# Interlock_Multiplexer.net
KiCad netlist of a schematic drawn in Altium Designer
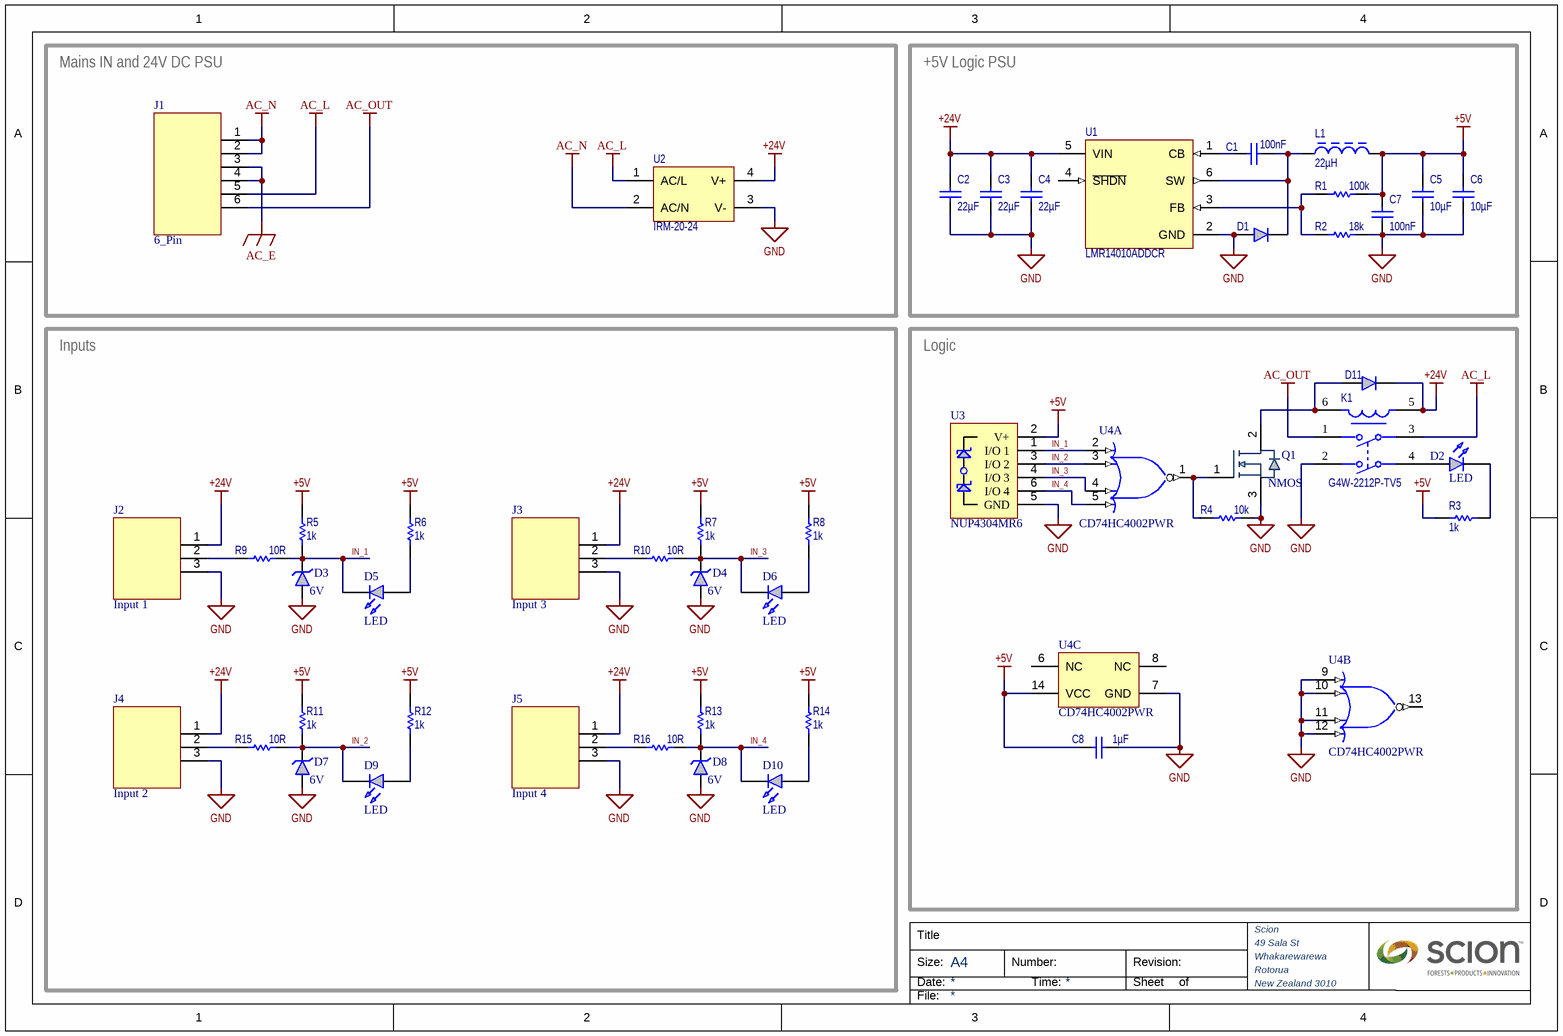
[diagram p0: Interlock Multiplexer.SchDoc]

(export (version "E")
  (design (tool "Eeschema 10.0.6"))
  (components
    (comp (ref "C1")
      (value "100nF")
      (footprint "0603_CAP")
      (description "SMD Capacitor")
      (fields (field (name "Comment") "Capacitor"))
      (libsource (lib "Scion Research") (part "CMP-019-00005-2"))
    )
    (comp (ref "C2")
      (value "22µF")
      (footprint "1206_CAP")
      (description "SMD Capacitor")
      (fields (field (name "Comment") "Capacitor"))
      (libsource (lib "Scion Research") (part "CMP-019-00005-2"))
    )
    (comp (ref "C3")
      (value "22µF")
      (footprint "1206_CAP")
      (description "SMD Capacitor")
      (fields (field (name "Comment") "Capacitor"))
      (libsource (lib "Scion Research") (part "CMP-019-00005-2"))
    )
    (comp (ref "C4")
      (value "22µF")
      (footprint "1206_CAP")
      (description "SMD Capacitor")
      (fields (field (name "Comment") "Capacitor"))
      (libsource (lib "Scion Research") (part "CMP-019-00005-2"))
    )
    (comp (ref "C5")
      (value "10µF")
      (footprint "0603_CAP")
      (description "SMD Capacitor")
      (fields (field (name "Comment") "Capacitor"))
      (libsource (lib "Scion Research") (part "CMP-019-00005-2"))
    )
    (comp (ref "C6")
      (value "10µF")
      (footprint "0603_CAP")
      (description "SMD Capacitor")
      (fields (field (name "Comment") "Capacitor"))
      (libsource (lib "Scion Research") (part "CMP-019-00005-2"))
    )
    (comp (ref "C7")
      (value "100nF")
      (footprint "0603_CAP")
      (description "SMD Capacitor")
      (fields (field (name "Comment") "Capacitor"))
      (libsource (lib "Scion Research") (part "CMP-019-00005-2"))
    )
    (comp (ref "C8")
      (value "1µF")
      (footprint "0603_CAP")
      (description "SMD Capacitor")
      (fields (field (name "Comment") "Capacitor"))
      (libsource (lib "Scion Research") (part "CMP-019-00005-2"))
    )
    (comp (ref "D1")
      (value "Diode")
      (footprint "SOD-123")
      (description "SMD Diode")
      (libsource (lib "Scion Research") (part "Diode"))
    )
    (comp (ref "D2")
      (value "LED")
      (footprint "0805")
      (description "SMD LED")
      (libsource (lib "Scion Research") (part "CMP-004-00032-1"))
    )
    (comp (ref "D3")
      (value "Transil")
      (footprint "SMBJ")
      (description "Transient Voltage Suppressor")
      (fields (field (name "RATED VOLTAGE") "6V"))
      (libsource (lib "Scion Research") (part "CMP-004-0042-1"))
    )
    (comp (ref "D4")
      (value "Transil")
      (footprint "SMBJ")
      (description "Transient Voltage Suppressor")
      (fields (field (name "RATED VOLTAGE") "6V"))
      (libsource (lib "Scion Research") (part "CMP-004-0042-1"))
    )
    (comp (ref "D5")
      (value "LED")
      (footprint "0805")
      (description "SMD LED")
      (libsource (lib "Scion Research") (part "CMP-004-00032-1"))
    )
    (comp (ref "D6")
      (value "LED")
      (footprint "0805")
      (description "SMD LED")
      (libsource (lib "Scion Research") (part "CMP-004-00032-1"))
    )
    (comp (ref "D7")
      (value "Transil")
      (footprint "SMBJ")
      (description "Transient Voltage Suppressor")
      (fields (field (name "RATED VOLTAGE") "6V"))
      (libsource (lib "Scion Research") (part "CMP-004-0042-1"))
    )
    (comp (ref "D8")
      (value "Transil")
      (footprint "SMBJ")
      (description "Transient Voltage Suppressor")
      (fields (field (name "RATED VOLTAGE") "6V"))
      (libsource (lib "Scion Research") (part "CMP-004-0042-1"))
    )
    (comp (ref "D9")
      (value "LED")
      (footprint "0805")
      (description "SMD LED")
      (libsource (lib "Scion Research") (part "CMP-004-00032-1"))
    )
    (comp (ref "D10")
      (value "LED")
      (footprint "0805")
      (description "SMD LED")
      (libsource (lib "Scion Research") (part "CMP-004-00032-1"))
    )
    (comp (ref "D11")
      (value "Diode")
      (footprint "SOD-123")
      (description "SMD Diode")
      (libsource (lib "Scion Research") (part "Diode"))
    )
    (comp (ref "J1")
      (value "6_Pin")
      (footprint "TDPT 6p 5.08")
      (description "6 Pin Connector")
      (libsource (lib "Scion Research") (part "CMP-002-00081-5"))
    )
    (comp (ref "J2")
      (value "Input 1")
      (footprint "3_Pin 3.81mm Molex 395111-003")
      (description "3 Pin Connector")
      (libsource (lib "Scion Research") (part "CMP-002-00075-6"))
    )
    (comp (ref "J3")
      (value "Input 3")
      (footprint "3_Pin 3.81mm Molex 395111-003")
      (description "3 Pin Connector")
      (libsource (lib "Scion Research") (part "CMP-002-00075-6"))
    )
    (comp (ref "J4")
      (value "Input 2")
      (footprint "3_Pin 3.81mm Molex 395111-003")
      (description "3 Pin Connector")
      (libsource (lib "Scion Research") (part "CMP-002-00075-6"))
    )
    (comp (ref "J5")
      (value "Input 4")
      (footprint "3_Pin 3.81mm Molex 395111-003")
      (description "3 Pin Connector")
      (libsource (lib "Scion Research") (part "CMP-002-00075-6"))
    )
    (comp (ref "K1")
      (value "G4W-2212P-TV5")
      (footprint "G4W-2212P-US-TV5 24VDC-Footprint-1")
      (description "DPNO 10A 24VDC Relay")
      (libsource (lib "Scion Research") (part "CMP-00056-1"))
    )
    (comp (ref "L1")
      (value "22µH")
      (footprint "BOUR-SRN8040_V")
      (description "Power Inductor")
      (fields (field (name "Comment") "Inductor"))
      (libsource (lib "Scion Research") (part "Inductor"))
    )
    (comp (ref "Q1")
      (value "NMOS")
      (footprint "SOT-23")
      (description "N Channel MOSFET")
      (libsource (lib "Scion Research") (part "CMP-004-0025-1"))
    )
    (comp (ref "R1")
      (value "Resistor")
      (footprint "0603_RES")
      (description "SMD Resistor")
      (fields (field (name "ALTIUM_VALUE") "100k"))
      (libsource (lib "Scion Research") (part "CMP-009-00177-2"))
    )
    (comp (ref "R2")
      (value "Resistor")
      (footprint "0603_RES")
      (description "SMD Resistor")
      (fields (field (name "ALTIUM_VALUE") "18k"))
      (libsource (lib "Scion Research") (part "CMP-009-00177-2"))
    )
    (comp (ref "R3")
      (value "Resistor")
      (footprint "0603_RES")
      (description "SMD Resistor")
      (fields (field (name "ALTIUM_VALUE") "1k"))
      (libsource (lib "Scion Research") (part "CMP-009-00177-2"))
    )
    (comp (ref "R4")
      (value "Resistor")
      (footprint "0603_RES")
      (description "SMD Resistor")
      (fields (field (name "ALTIUM_VALUE") "10k"))
      (libsource (lib "Scion Research") (part "CMP-009-00177-2"))
    )
    (comp (ref "R5")
      (value "Resistor")
      (footprint "0603_RES")
      (description "SMD Resistor")
      (fields (field (name "ALTIUM_VALUE") "1k"))
      (libsource (lib "Scion Research") (part "CMP-009-00177-2"))
    )
    (comp (ref "R6")
      (value "Resistor")
      (footprint "0603_RES")
      (description "SMD Resistor")
      (fields (field (name "ALTIUM_VALUE") "1k"))
      (libsource (lib "Scion Research") (part "CMP-009-00177-2"))
    )
    (comp (ref "R7")
      (value "Resistor")
      (footprint "0603_RES")
      (description "SMD Resistor")
      (fields (field (name "ALTIUM_VALUE") "1k"))
      (libsource (lib "Scion Research") (part "CMP-009-00177-2"))
    )
    (comp (ref "R8")
      (value "Resistor")
      (footprint "0603_RES")
      (description "SMD Resistor")
      (fields (field (name "ALTIUM_VALUE") "1k"))
      (libsource (lib "Scion Research") (part "CMP-009-00177-2"))
    )
    (comp (ref "R9")
      (value "Resistor")
      (footprint "0603_RES")
      (description "SMD Resistor")
      (fields (field (name "ALTIUM_VALUE") "10R"))
      (libsource (lib "Scion Research") (part "CMP-009-00177-2"))
    )
    (comp (ref "R10")
      (value "Resistor")
      (footprint "0603_RES")
      (description "SMD Resistor")
      (fields (field (name "ALTIUM_VALUE") "10R"))
      (libsource (lib "Scion Research") (part "CMP-009-00177-2"))
    )
    (comp (ref "R11")
      (value "Resistor")
      (footprint "0603_RES")
      (description "SMD Resistor")
      (fields (field (name "ALTIUM_VALUE") "1k"))
      (libsource (lib "Scion Research") (part "CMP-009-00177-2"))
    )
    (comp (ref "R12")
      (value "Resistor")
      (footprint "0603_RES")
      (description "SMD Resistor")
      (fields (field (name "ALTIUM_VALUE") "1k"))
      (libsource (lib "Scion Research") (part "CMP-009-00177-2"))
    )
    (comp (ref "R13")
      (value "Resistor")
      (footprint "0603_RES")
      (description "SMD Resistor")
      (fields (field (name "ALTIUM_VALUE") "1k"))
      (libsource (lib "Scion Research") (part "CMP-009-00177-2"))
    )
    (comp (ref "R14")
      (value "Resistor")
      (footprint "0603_RES")
      (description "SMD Resistor")
      (fields (field (name "ALTIUM_VALUE") "1k"))
      (libsource (lib "Scion Research") (part "CMP-009-00177-2"))
    )
    (comp (ref "R15")
      (value "Resistor")
      (footprint "0603_RES")
      (description "SMD Resistor")
      (fields (field (name "ALTIUM_VALUE") "10R"))
      (libsource (lib "Scion Research") (part "CMP-009-00177-2"))
    )
    (comp (ref "R16")
      (value "Resistor")
      (footprint "0603_RES")
      (description "SMD Resistor")
      (fields (field (name "ALTIUM_VALUE") "10R"))
      (libsource (lib "Scion Research") (part "CMP-009-00177-2"))
    )
    (comp (ref "U1")
      (value "LMR14010ADDCR")
      (footprint "FP-DDC0006A-IPC_A")
      (description "7-40VDC-DC buck converter")
      (libsource (lib "Scion Research") (part "LMR14010"))
    )
    (comp (ref "U2")
      (value "IRM-20-24")
      (footprint "IRM-20-24-Footprint-1")
      (description "AC/DC 20W 24V Single Output Power Supply, Encapsulated Board Mount Module")
      (libsource (lib "Scion Research") (part "CMP-00053-2"))
    )
    (comp (ref "U3")
      (value "NUP4304MR6")
      (footprint "TSOP-6")
      (description "ESD Protection Doide Array")
      (libsource (lib "Scion Research") (part "CMP-004-0028-1"))
    )
    (comp (ref "U4")
      (value "CD74HC4002PWR")
      (footprint "PW0014A_N")
      (description "NOR Gate, HC Series, 2-Func, 4-Input, CMOS, PDSO14")
      (libsource (lib "Scion Research") (part "TI-CD_SNX4HC4002-14"))
    )
  )
  (nets
    (net (code "1") (name "+5V") (class "Default")
      (node (ref "C5") (pin "1") (pinfunction "1_1") (pintype "passive"))
      (node (ref "C6") (pin "1") (pinfunction "1_1") (pintype "passive"))
      (node (ref "C7") (pin "1") (pinfunction "1_1") (pintype "passive"))
      (node (ref "C8") (pin "1") (pinfunction "1_1") (pintype "passive"))
      (node (ref "L1") (pin "2") (pinfunction "2_2") (pintype "passive"))
      (node (ref "R1") (pin "2") (pinfunction "2_2") (pintype "passive"))
      (node (ref "R11") (pin "2") (pinfunction "2_2") (pintype "passive"))
      (node (ref "R12") (pin "2") (pinfunction "2_2") (pintype "passive"))
      (node (ref "R13") (pin "2") (pinfunction "2_2") (pintype "passive"))
      (node (ref "R14") (pin "2") (pinfunction "2_2") (pintype "passive"))
      (node (ref "R3") (pin "2") (pinfunction "2_2") (pintype "passive"))
      (node (ref "R5") (pin "2") (pinfunction "2_2") (pintype "passive"))
      (node (ref "R6") (pin "2") (pinfunction "2_2") (pintype "passive"))
      (node (ref "R7") (pin "2") (pinfunction "2_2") (pintype "passive"))
      (node (ref "R8") (pin "2") (pinfunction "2_2") (pintype "passive"))
      (node (ref "U3") (pin "2") (pinfunction "V+_2") (pintype "power_in"))
      (node (ref "U4") (pin "14") (pinfunction "VCC_14") (pintype "power_in"))
    )
    (net (code "2") (name "+24V") (class "Default")
      (node (ref "C2") (pin "1") (pinfunction "1_1") (pintype "passive"))
      (node (ref "C3") (pin "1") (pinfunction "1_1") (pintype "passive"))
      (node (ref "C4") (pin "1") (pinfunction "1_1") (pintype "passive"))
      (node (ref "D11") (pin "1") (pinfunction "K_1") (pintype "passive"))
      (node (ref "J2") (pin "1") (pinfunction "1_1") (pintype "passive"))
      (node (ref "J3") (pin "1") (pinfunction "1_1") (pintype "passive"))
      (node (ref "J4") (pin "1") (pinfunction "1_1") (pintype "passive"))
      (node (ref "J5") (pin "1") (pinfunction "1_1") (pintype "passive"))
      (node (ref "K1") (pin "5") (pinfunction "5_5") (pintype "passive"))
      (node (ref "U1") (pin "5") (pinfunction "VIN_5") (pintype "power_in"))
      (node (ref "U2") (pin "4") (pinfunction "V+_4") (pintype "power_in"))
    )
    (net (code "3") (name "/IN_1") (class "Default")
      (node (ref "D3") (pin "2") (pinfunction "K_2") (pintype "passive"))
      (node (ref "D5") (pin "1") (pinfunction "K_1") (pintype "passive"))
      (node (ref "R5") (pin "1") (pinfunction "1_1") (pintype "passive"))
      (node (ref "R9") (pin "2") (pinfunction "2_2") (pintype "passive"))
      (node (ref "U3") (pin "1") (pinfunction "I/O_1_1") (pintype "power_in"))
      (node (ref "U4") (pin "2") (pinfunction "1A_2") (pintype "input"))
    )
    (net (code "4") (name "/IN_2") (class "Default")
      (node (ref "D7") (pin "2") (pinfunction "K_2") (pintype "passive"))
      (node (ref "D9") (pin "1") (pinfunction "K_1") (pintype "passive"))
      (node (ref "R11") (pin "1") (pinfunction "1_1") (pintype "passive"))
      (node (ref "R15") (pin "2") (pinfunction "2_2") (pintype "passive"))
      (node (ref "U3") (pin "3") (pinfunction "I/O_2_3") (pintype "power_in"))
      (node (ref "U4") (pin "3") (pinfunction "1B_3") (pintype "input"))
    )
    (net (code "5") (name "/IN_3") (class "Default")
      (node (ref "D4") (pin "2") (pinfunction "K_2") (pintype "passive"))
      (node (ref "D6") (pin "1") (pinfunction "K_1") (pintype "passive"))
      (node (ref "R10") (pin "2") (pinfunction "2_2") (pintype "passive"))
      (node (ref "R7") (pin "1") (pinfunction "1_1") (pintype "passive"))
      (node (ref "U3") (pin "4") (pinfunction "I/O_3_4") (pintype "power_in"))
      (node (ref "U4") (pin "4") (pinfunction "1C_4") (pintype "input"))
    )
    (net (code "6") (name "/IN_4") (class "Default")
      (node (ref "D10") (pin "1") (pinfunction "K_1") (pintype "passive"))
      (node (ref "D8") (pin "2") (pinfunction "K_2") (pintype "passive"))
      (node (ref "R13") (pin "1") (pinfunction "1_1") (pintype "passive"))
      (node (ref "R16") (pin "2") (pinfunction "2_2") (pintype "passive"))
      (node (ref "U3") (pin "6") (pinfunction "I/O_4_6") (pintype "power_in"))
      (node (ref "U4") (pin "5") (pinfunction "1D_5") (pintype "input"))
    )
    (net (code "7") (name "AC_E") (class "Default")
      (node (ref "J1") (pin "3") (pinfunction "3_3") (pintype "passive"))
      (node (ref "J1") (pin "4") (pinfunction "4_4") (pintype "passive"))
    )
    (net (code "8") (name "AC_L") (class "Default")
      (node (ref "J1") (pin "5") (pinfunction "5_5") (pintype "passive"))
      (node (ref "K1") (pin "3") (pinfunction "3_3") (pintype "passive"))
      (node (ref "U2") (pin "1") (pinfunction "AC/L_1") (pintype "passive"))
    )
    (net (code "9") (name "AC_N") (class "Default")
      (node (ref "J1") (pin "1") (pinfunction "1_1") (pintype "passive"))
      (node (ref "J1") (pin "2") (pinfunction "2_2") (pintype "passive"))
      (node (ref "U2") (pin "2") (pinfunction "AC/N_2") (pintype "passive"))
    )
    (net (code "10") (name "AC_OUT") (class "Default")
      (node (ref "J1") (pin "6") (pinfunction "6_6") (pintype "passive"))
      (node (ref "K1") (pin "1") (pinfunction "1_1") (pintype "passive"))
    )
    (net (code "11") (name "GND") (class "Default")
      (node (ref "C2") (pin "2") (pinfunction "2_2") (pintype "passive"))
      (node (ref "C3") (pin "2") (pinfunction "2_2") (pintype "passive"))
      (node (ref "C4") (pin "2") (pinfunction "2_2") (pintype "passive"))
      (node (ref "C5") (pin "2") (pinfunction "2_2") (pintype "passive"))
      (node (ref "C6") (pin "2") (pinfunction "2_2") (pintype "passive"))
      (node (ref "C7") (pin "2") (pinfunction "2_2") (pintype "passive"))
      (node (ref "C8") (pin "2") (pinfunction "2_2") (pintype "passive"))
      (node (ref "D1") (pin "2") (pinfunction "A_2") (pintype "passive"))
      (node (ref "D3") (pin "1") (pinfunction "A_1") (pintype "passive"))
      (node (ref "D4") (pin "1") (pinfunction "A_1") (pintype "passive"))
      (node (ref "D7") (pin "1") (pinfunction "A_1") (pintype "passive"))
      (node (ref "D8") (pin "1") (pinfunction "A_1") (pintype "passive"))
      (node (ref "J2") (pin "3") (pinfunction "3_3") (pintype "passive"))
      (node (ref "J3") (pin "3") (pinfunction "3_3") (pintype "passive"))
      (node (ref "J4") (pin "3") (pinfunction "3_3") (pintype "passive"))
      (node (ref "J5") (pin "3") (pinfunction "3_3") (pintype "passive"))
      (node (ref "K1") (pin "2") (pinfunction "2_2") (pintype "passive"))
      (node (ref "Q1") (pin "3") (pinfunction "S_3") (pintype "passive"))
      (node (ref "R2") (pin "2") (pinfunction "2_2") (pintype "passive"))
      (node (ref "R4") (pin "2") (pinfunction "2_2") (pintype "passive"))
      (node (ref "U1") (pin "2") (pinfunction "GND_2") (pintype "power_in"))
      (node (ref "U2") (pin "3") (pinfunction "V-_3") (pintype "power_in"))
      (node (ref "U3") (pin "5") (pinfunction "GND_5") (pintype "power_in"))
      (node (ref "U4") (pin "10") (pinfunction "2B_10") (pintype "input"))
      (node (ref "U4") (pin "11") (pinfunction "2C_11") (pintype "input"))
      (node (ref "U4") (pin "12") (pinfunction "2D_12") (pintype "input"))
      (node (ref "U4") (pin "7") (pinfunction "GND_7") (pintype "power_in"))
      (node (ref "U4") (pin "9") (pinfunction "2A_9") (pintype "input"))
    )
    (net (code "12") (name "Net-(D1-K)") (class "Default")
      (node (ref "C1") (pin "1") (pinfunction "1_1") (pintype "passive"))
      (node (ref "D1") (pin "1") (pinfunction "K_1") (pintype "passive"))
      (node (ref "L1") (pin "1") (pinfunction "1_1") (pintype "passive"))
      (node (ref "U1") (pin "6") (pinfunction "SW_6") (pintype "output"))
    )
    (net (code "13") (name "Net-(D2-A)") (class "Default")
      (node (ref "D2") (pin "2") (pinfunction "A_2") (pintype "passive"))
      (node (ref "K1") (pin "4") (pinfunction "4_4") (pintype "passive"))
    )
    (net (code "14") (name "Net-(D2-K)") (class "Default")
      (node (ref "D2") (pin "1") (pinfunction "K_1") (pintype "passive"))
      (node (ref "R3") (pin "1") (pinfunction "1_1") (pintype "passive"))
    )
    (net (code "15") (name "Net-(D5-A)") (class "Default")
      (node (ref "D5") (pin "2") (pinfunction "A_2") (pintype "passive"))
      (node (ref "R6") (pin "1") (pinfunction "1_1") (pintype "passive"))
    )
    (net (code "16") (name "Net-(D6-A)") (class "Default")
      (node (ref "D6") (pin "2") (pinfunction "A_2") (pintype "passive"))
      (node (ref "R8") (pin "1") (pinfunction "1_1") (pintype "passive"))
    )
    (net (code "17") (name "Net-(D9-A)") (class "Default")
      (node (ref "D9") (pin "2") (pinfunction "A_2") (pintype "passive"))
      (node (ref "R12") (pin "1") (pinfunction "1_1") (pintype "passive"))
    )
    (net (code "18") (name "Net-(D10-A)") (class "Default")
      (node (ref "D10") (pin "2") (pinfunction "A_2") (pintype "passive"))
      (node (ref "R14") (pin "1") (pinfunction "1_1") (pintype "passive"))
    )
    (net (code "19") (name "Net-(D11-A)") (class "Default")
      (node (ref "D11") (pin "2") (pinfunction "A_2") (pintype "passive"))
      (node (ref "K1") (pin "6") (pinfunction "6_6") (pintype "passive"))
      (node (ref "Q1") (pin "2") (pinfunction "D_2") (pintype "passive"))
    )
    (net (code "20") (name "Net-(J2-Pad2)") (class "Default")
      (node (ref "J2") (pin "2") (pinfunction "2_2") (pintype "passive"))
      (node (ref "R9") (pin "1") (pinfunction "1_1") (pintype "passive"))
    )
    (net (code "21") (name "Net-(J3-Pad2)") (class "Default")
      (node (ref "J3") (pin "2") (pinfunction "2_2") (pintype "passive"))
      (node (ref "R10") (pin "1") (pinfunction "1_1") (pintype "passive"))
    )
    (net (code "22") (name "Net-(J4-Pad2)") (class "Default")
      (node (ref "J4") (pin "2") (pinfunction "2_2") (pintype "passive"))
      (node (ref "R15") (pin "1") (pinfunction "1_1") (pintype "passive"))
    )
    (net (code "23") (name "Net-(J5-Pad2)") (class "Default")
      (node (ref "J5") (pin "2") (pinfunction "2_2") (pintype "passive"))
      (node (ref "R16") (pin "1") (pinfunction "1_1") (pintype "passive"))
    )
    (net (code "24") (name "Net-(Q1-G)") (class "Default")
      (node (ref "Q1") (pin "1") (pinfunction "G_1") (pintype "passive"))
      (node (ref "R4") (pin "1") (pinfunction "1_1") (pintype "passive"))
      (node (ref "U4") (pin "1") (pinfunction "1Y_1") (pintype "output"))
    )
    (net (code "25") (name "Net-(U1-CB)") (class "Default")
      (node (ref "C1") (pin "2") (pinfunction "2_2") (pintype "passive"))
      (node (ref "U1") (pin "1") (pinfunction "CB_1") (pintype "input"))
    )
    (net (code "26") (name "Net-(U1-FB)") (class "Default")
      (node (ref "R1") (pin "1") (pinfunction "1_1") (pintype "passive"))
      (node (ref "R2") (pin "1") (pinfunction "1_1") (pintype "passive"))
      (node (ref "U1") (pin "3") (pinfunction "FB_3") (pintype "input"))
    )
    (net (code "27") (name "unconnected-(U1-~{SHDN}-Pad4)") (class "Default")
      (node (ref "U1") (pin "4") (pinfunction "~{SHDN}_4") (pintype "input"))
    )
    (net (code "28") (name "unconnected-(U4B-2Y-Pad13)") (class "Default")
      (node (ref "U4") (pin "13") (pinfunction "2Y_13") (pintype "output"))
    )
    (net (code "29") (name "unconnected-(U4C-NC-Pad6)") (class "Default")
      (node (ref "U4") (pin "6") (pinfunction "NC_6") (pintype "passive"))
    )
    (net (code "30") (name "unconnected-(U4C-NC-Pad8)") (class "Default")
      (node (ref "U4") (pin "8") (pinfunction "NC_8") (pintype "passive"))
    )
  )
)
